# CZ_ESP32_Schematic.net
KiCad netlist of a schematic drawn in Altium Designer
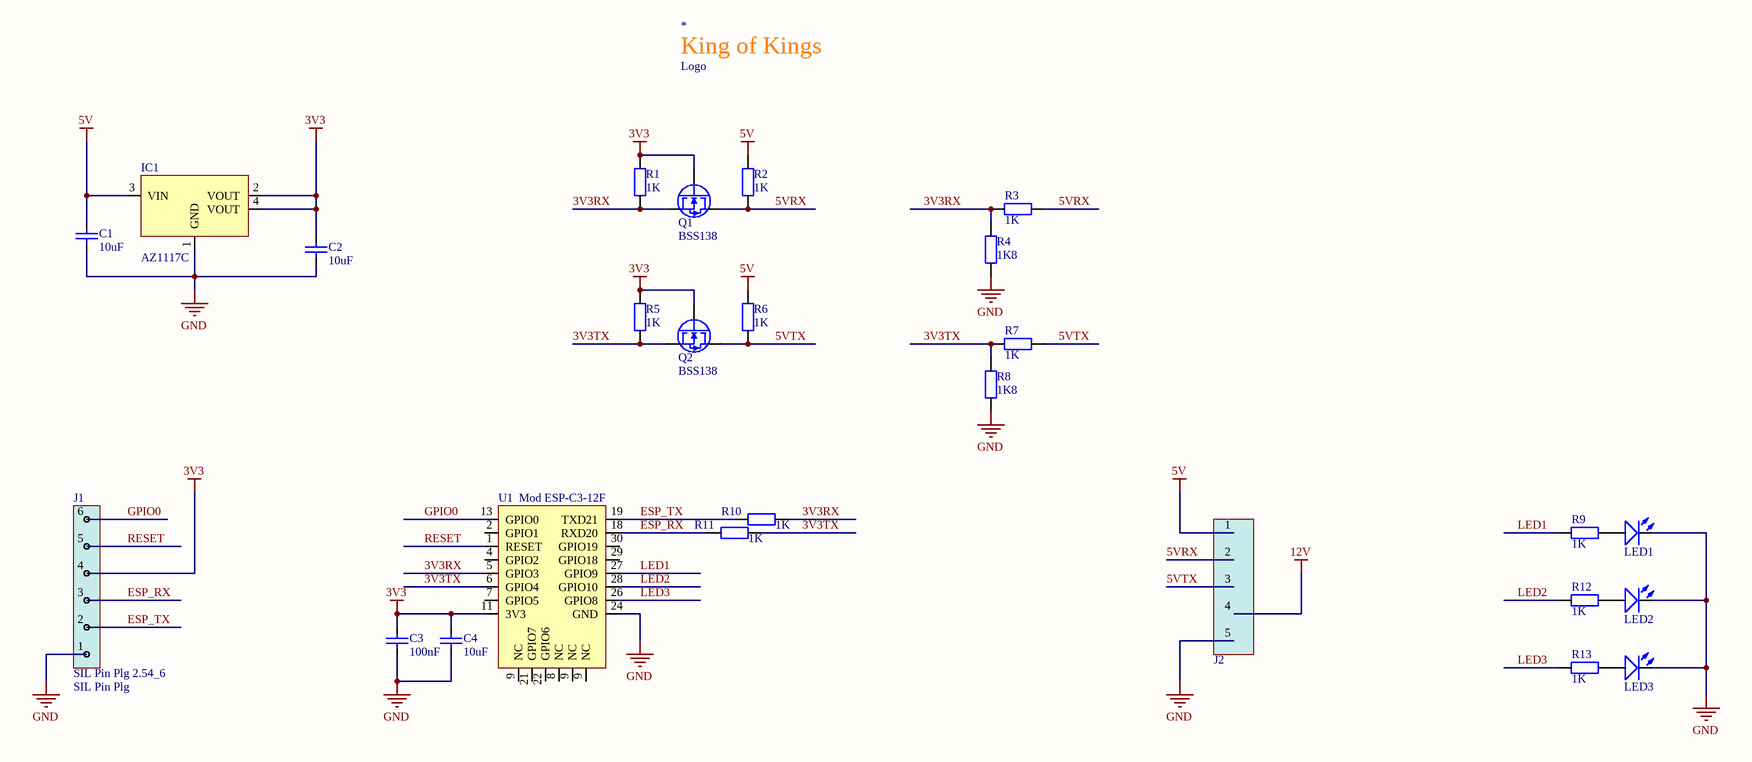
[diagram p0: CZ ESP32 Schematic.SchDoc]

(export (version "E")
  (design (tool "Eeschema 10.0.6"))
  (components
    (comp (ref "*")
      (value "Logo")
      (footprint "KingofKingsSmall")
      (libsource (lib "Neds Altium Lib") (part "Logo"))
    )
    (comp (ref "C1")
      (value "10uF")
      (footprint "Cap - 0805 - SML")
      (description "Cap SMD Ceramic")
      (libsource (lib "Neds Altium Lib") (part "Cap SMD Ceramic"))
    )
    (comp (ref "C2")
      (value "10uF")
      (footprint "Cap - 0805 - SML")
      (description "Cap SMD Ceramic")
      (libsource (lib "Neds Altium Lib") (part "Cap SMD Ceramic"))
    )
    (comp (ref "C3")
      (value "100nF")
      (footprint "Cap - 0805 - SML")
      (description "Cap SMD Ceramic")
      (libsource (lib "Neds Altium Lib") (part "Cap SMD Ceramic"))
    )
    (comp (ref "C4")
      (value "10uF")
      (footprint "Cap - 0805 - SML")
      (description "Cap SMD Ceramic")
      (libsource (lib "Neds Altium Lib") (part "Cap SMD Ceramic"))
    )
    (comp (ref "IC1")
      (value "AZ1117C")
      (footprint "sot223-4")
      (description "IC REG LINEAR 3.3V 800MA SOT223")
      (fields (field (name "MANUFACTURER PART NUMBER") "AZ1117CH-3.3TRG1"))
      (libsource (lib "Neds Altium Lib") (part "IC REG AZ1117CH-3.3"))
    )
    (comp (ref "J1")
      (value "SIL Pin Plg 2.54_6")
      (footprint "SIL PIN PLG 2.54_6")
      (description "6 Way SIL Pins")
      (fields (field (name "VOLTAGE") "250V") (field (name "TYPE") "SIL Pin Plg"))
      (libsource (lib "Connectors_SIL") (part "SIL Pin Plg 2.54_6"))
    )
    (comp (ref "J2")
      (value "JST-PA")
      (footprint "JST PA-5 2mm RA")
      (libsource (lib "Neds Altium Lib") (part "Conn JST PA SM05B"))
    )
    (comp (ref "LED1")
      (value "LTST-C190EKT")
      (footprint "LTST-C190EKT")
      (description "LED RED CLEAR 0603 SMD")
      (libsource (lib "Neds Altium Lib") (part "LTST-C190EKT"))
    )
    (comp (ref "LED2")
      (value "LTST-C190EKT")
      (footprint "LTST-C190EKT")
      (description "LED RED CLEAR 0603 SMD")
      (libsource (lib "Neds Altium Lib") (part "LTST-C190EKT"))
    )
    (comp (ref "LED3")
      (value "LTST-C190EKT")
      (footprint "LTST-C190EKT")
      (description "LED RED CLEAR 0603 SMD")
      (libsource (lib "Neds Altium Lib") (part "LTST-C190EKT"))
    )
    (comp (ref "Q1")
      (value "BSS138")
      (footprint "SOT23-3")
      (description "MOSFET N-CH 50V 220MA SOT23-3")
      (libsource (lib "Neds Altium Lib") (part "N-FET 50V 0.22A"))
    )
    (comp (ref "Q2")
      (value "BSS138")
      (footprint "SOT23-3")
      (description "MOSFET N-CH 50V 220MA SOT23-3")
      (libsource (lib "Neds Altium Lib") (part "N-FET 50V 0.22A"))
    )
    (comp (ref "R1")
      (value "1K")
      (footprint "Res - 0603 - SML")
      (description "Res SMD")
      (libsource (lib "Neds Altium Lib") (part "Res SMD"))
    )
    (comp (ref "R2")
      (value "1K")
      (footprint "Res - 0603 - SML")
      (description "Res SMD")
      (libsource (lib "Neds Altium Lib") (part "Res SMD"))
    )
    (comp (ref "R3")
      (value "1K")
      (footprint "Res - 0603 - SML")
      (description "Res SMD")
      (libsource (lib "") (part "Res SMD_1"))
    )
    (comp (ref "R4")
      (value "1K8")
      (footprint "Res - 0603 - SML")
      (description "Res SMD")
      (libsource (lib "Neds Altium Lib") (part "Res SMD"))
    )
    (comp (ref "R5")
      (value "1K")
      (footprint "Res - 0603 - SML")
      (description "Res SMD")
      (libsource (lib "Neds Altium Lib") (part "Res SMD"))
    )
    (comp (ref "R6")
      (value "1K")
      (footprint "Res - 0603 - SML")
      (description "Res SMD")
      (libsource (lib "Neds Altium Lib") (part "Res SMD"))
    )
    (comp (ref "R7")
      (value "1K")
      (footprint "Res - 0603 - SML")
      (description "Res SMD")
      (libsource (lib "") (part "Res SMD_1"))
    )
    (comp (ref "R8")
      (value "1K8")
      (footprint "Res - 0603 - SML")
      (description "Res SMD")
      (libsource (lib "Neds Altium Lib") (part "Res SMD"))
    )
    (comp (ref "R9")
      (value "1K")
      (footprint "Res - 0603 - SML")
      (description "Res SMD")
      (libsource (lib "") (part "Res SMD_2"))
    )
    (comp (ref "R10")
      (value "1K")
      (footprint "Res - 0603 - SML")
      (description "Res SMD")
      (libsource (lib "") (part "Res SMD_1"))
    )
    (comp (ref "R11")
      (value "1K")
      (footprint "Res - 0603 - SML")
      (description "Res SMD")
      (libsource (lib "") (part "Res SMD_1"))
    )
    (comp (ref "R12")
      (value "1K")
      (footprint "Res - 0603 - SML")
      (description "Res SMD")
      (libsource (lib "") (part "Res SMD_2"))
    )
    (comp (ref "R13")
      (value "1K")
      (footprint "Res - 0603 - SML")
      (description "Res SMD")
      (libsource (lib "") (part "Res SMD_2"))
    )
    (comp (ref "U1")
      (value "Mod ESP-C3-12F")
      (footprint "ESP-C3-12F")
      (libsource (lib "Neds Altium Lib") (part "Mod ESP-C3-12F"))
    )
  )
  (nets
    (net (code "1") (name "/3V3RX") (class "Default")
      (node (ref "Q1") (pin "2") (pinfunction "Source_2") (pintype "passive"))
      (node (ref "R1") (pin "1") (pintype "passive"))
      (node (ref "R10") (pin "1") (pintype "passive"))
      (node (ref "R3") (pin "2") (pintype "passive"))
      (node (ref "R4") (pin "2") (pintype "passive"))
      (node (ref "U1") (pin "5") (pinfunction "GPIO3_5") (pintype "power_in"))
    )
    (net (code "2") (name "/3V3TX") (class "Default")
      (node (ref "Q2") (pin "2") (pinfunction "Source_2") (pintype "passive"))
      (node (ref "R11") (pin "1") (pintype "passive"))
      (node (ref "R5") (pin "1") (pintype "passive"))
      (node (ref "R7") (pin "2") (pintype "passive"))
      (node (ref "R8") (pin "2") (pintype "passive"))
      (node (ref "U1") (pin "6") (pinfunction "GPIO4_6") (pintype "power_in"))
    )
    (net (code "3") (name "/5VRX") (class "Default")
      (node (ref "J2") (pin "2") (pinfunction "2_2") (pintype "passive"))
      (node (ref "Q1") (pin "3") (pinfunction "Drain_3") (pintype "passive"))
      (node (ref "R2") (pin "1") (pintype "passive"))
      (node (ref "R3") (pin "1") (pintype "passive"))
    )
    (net (code "4") (name "/5VTX") (class "Default")
      (node (ref "J2") (pin "3") (pinfunction "3_3") (pintype "passive"))
      (node (ref "Q2") (pin "3") (pinfunction "Drain_3") (pintype "passive"))
      (node (ref "R6") (pin "1") (pintype "passive"))
      (node (ref "R7") (pin "1") (pintype "passive"))
    )
    (net (code "5") (name "/ESP_RX") (class "Default")
      (node (ref "J1") (pin "3") (pinfunction "3_3") (pintype "passive"))
      (node (ref "R11") (pin "2") (pintype "passive"))
      (node (ref "U1") (pin "18") (pinfunction "RXD20_18") (pintype "power_in"))
    )
    (net (code "6") (name "/ESP_TX") (class "Default")
      (node (ref "J1") (pin "2") (pinfunction "2_2") (pintype "passive"))
      (node (ref "R10") (pin "2") (pintype "passive"))
      (node (ref "U1") (pin "19") (pinfunction "TXD21_19") (pintype "power_in"))
    )
    (net (code "7") (name "/GPIO0") (class "Default")
      (node (ref "J1") (pin "6") (pinfunction "6_6") (pintype "passive"))
      (node (ref "U1") (pin "13") (pinfunction "GPIO0_13") (pintype "power_in"))
    )
    (net (code "8") (name "/LED1") (class "Default")
      (node (ref "R9") (pin "1") (pintype "passive"))
      (node (ref "U1") (pin "27") (pinfunction "GPIO9_27") (pintype "power_in"))
    )
    (net (code "9") (name "/LED2") (class "Default")
      (node (ref "R12") (pin "1") (pintype "passive"))
      (node (ref "U1") (pin "28") (pinfunction "GPIO10_28") (pintype "power_in"))
    )
    (net (code "10") (name "/LED3") (class "Default")
      (node (ref "R13") (pin "1") (pintype "passive"))
      (node (ref "U1") (pin "26") (pinfunction "GPIO8_26") (pintype "power_in"))
    )
    (net (code "11") (name "/RESET") (class "Default")
      (node (ref "J1") (pin "5") (pinfunction "5_5") (pintype "passive"))
      (node (ref "U1") (pin "1") (pinfunction "RESET_1") (pintype "power_in"))
    )
    (net (code "12") (name "3V3") (class "Default")
      (node (ref "C2") (pin "2") (pinfunction "2_2") (pintype "passive"))
      (node (ref "C3") (pin "2") (pinfunction "2_2") (pintype "passive"))
      (node (ref "C4") (pin "2") (pinfunction "2_2") (pintype "passive"))
      (node (ref "IC1") (pin "2") (pinfunction "VOUT_2") (pintype "power_in"))
      (node (ref "IC1") (pin "4") (pinfunction "VOUT_4") (pintype "power_in"))
      (node (ref "J1") (pin "4") (pinfunction "4_4") (pintype "passive"))
      (node (ref "Q1") (pin "1") (pinfunction "Gate_1") (pintype "passive"))
      (node (ref "Q2") (pin "1") (pinfunction "Gate_1") (pintype "passive"))
      (node (ref "R1") (pin "2") (pintype "passive"))
      (node (ref "R5") (pin "2") (pintype "passive"))
      (node (ref "U1") (pin "11") (pinfunction "3V3_11") (pintype "power_in"))
    )
    (net (code "13") (name "5V") (class "Default")
      (node (ref "C1") (pin "2") (pinfunction "2_2") (pintype "passive"))
      (node (ref "IC1") (pin "3") (pinfunction "VIN_3") (pintype "power_in"))
      (node (ref "J2") (pin "1") (pinfunction "1_1") (pintype "passive"))
      (node (ref "R2") (pin "2") (pintype "passive"))
      (node (ref "R6") (pin "2") (pintype "passive"))
    )
    (net (code "14") (name "12V") (class "Default")
      (node (ref "J2") (pin "4") (pinfunction "4_4") (pintype "passive"))
    )
    (net (code "15") (name "GND") (class "Default")
      (node (ref "C1") (pin "1") (pinfunction "1_1") (pintype "passive"))
      (node (ref "C2") (pin "1") (pinfunction "1_1") (pintype "passive"))
      (node (ref "C3") (pin "1") (pinfunction "1_1") (pintype "passive"))
      (node (ref "C4") (pin "1") (pinfunction "1_1") (pintype "passive"))
      (node (ref "IC1") (pin "1") (pinfunction "GND_1") (pintype "power_in"))
      (node (ref "J1") (pin "1") (pinfunction "1_1") (pintype "passive"))
      (node (ref "J2") (pin "5") (pinfunction "5_5") (pintype "passive"))
      (node (ref "LED1") (pin "2") (pinfunction "Cathode_2") (pintype "passive"))
      (node (ref "LED2") (pin "2") (pinfunction "Cathode_2") (pintype "passive"))
      (node (ref "LED3") (pin "2") (pinfunction "Cathode_2") (pintype "passive"))
      (node (ref "R4") (pin "1") (pintype "passive"))
      (node (ref "R8") (pin "1") (pintype "passive"))
      (node (ref "U1") (pin "24") (pinfunction "GND_24") (pintype "power_in"))
    )
    (net (code "16") (name "Net-(LED1-Anode)") (class "Default")
      (node (ref "LED1") (pin "1") (pinfunction "Anode_1") (pintype "passive"))
      (node (ref "R9") (pin "2") (pintype "passive"))
    )
    (net (code "17") (name "Net-(LED2-Anode)") (class "Default")
      (node (ref "LED2") (pin "1") (pinfunction "Anode_1") (pintype "passive"))
      (node (ref "R12") (pin "2") (pintype "passive"))
    )
    (net (code "18") (name "Net-(LED3-Anode)") (class "Default")
      (node (ref "LED3") (pin "1") (pinfunction "Anode_1") (pintype "passive"))
      (node (ref "R13") (pin "2") (pintype "passive"))
    )
    (net (code "19") (name "unconnected-(U1-GPIO1-Pad2)") (class "Default")
      (node (ref "U1") (pin "2") (pinfunction "GPIO1_2") (pintype "power_in"))
    )
    (net (code "20") (name "unconnected-(U1-GPIO2-Pad4)") (class "Default")
      (node (ref "U1") (pin "4") (pinfunction "GPIO2_4") (pintype "power_in"))
    )
    (net (code "21") (name "unconnected-(U1-GPIO5-Pad7)") (class "Default")
      (node (ref "U1") (pin "7") (pinfunction "GPIO5_7") (pintype "power_in"))
    )
    (net (code "22") (name "unconnected-(U1-GPIO6-Pad22)") (class "Default")
      (node (ref "U1") (pin "22") (pinfunction "GPIO6_22") (pintype "power_in"))
    )
    (net (code "23") (name "unconnected-(U1-GPIO7-Pad21)") (class "Default")
      (node (ref "U1") (pin "21") (pinfunction "GPIO7_21") (pintype "power_in"))
    )
    (net (code "24") (name "unconnected-(U1-GPIO18-Pad29)") (class "Default")
      (node (ref "U1") (pin "29") (pinfunction "GPIO18_29") (pintype "power_in"))
    )
    (net (code "25") (name "unconnected-(U1-GPIO19-Pad30)") (class "Default")
      (node (ref "U1") (pin "30") (pinfunction "GPIO19_30") (pintype "power_in"))
    )
    (net (code "26") (name "unconnected-(U1-NC-Pad8)") (class "Default")
      (node (ref "U1") (pin "8") (pinfunction "NC_8") (pintype "power_in"))
    )
    (net (code "27") (name "unconnected-(U1-NC-Pad9)") (class "Default")
      (node (ref "U1") (pin "9") (pinfunction "NC_9") (pintype "power_in"))
    )
    (net (code "28") (name "unconnected-(U1-NC-Pad9)_1") (class "Default")
      (node (ref "U1") (pin "9") (pinfunction "NC_9") (pintype "power_in"))
    )
    (net (code "29") (name "unconnected-(U1-NC-Pad9)_2") (class "Default")
      (node (ref "U1") (pin "9") (pinfunction "NC_9") (pintype "power_in"))
    )
  )
)
